# 11A-10.net
KiCad netlist of a schematic drawn in EAGLE
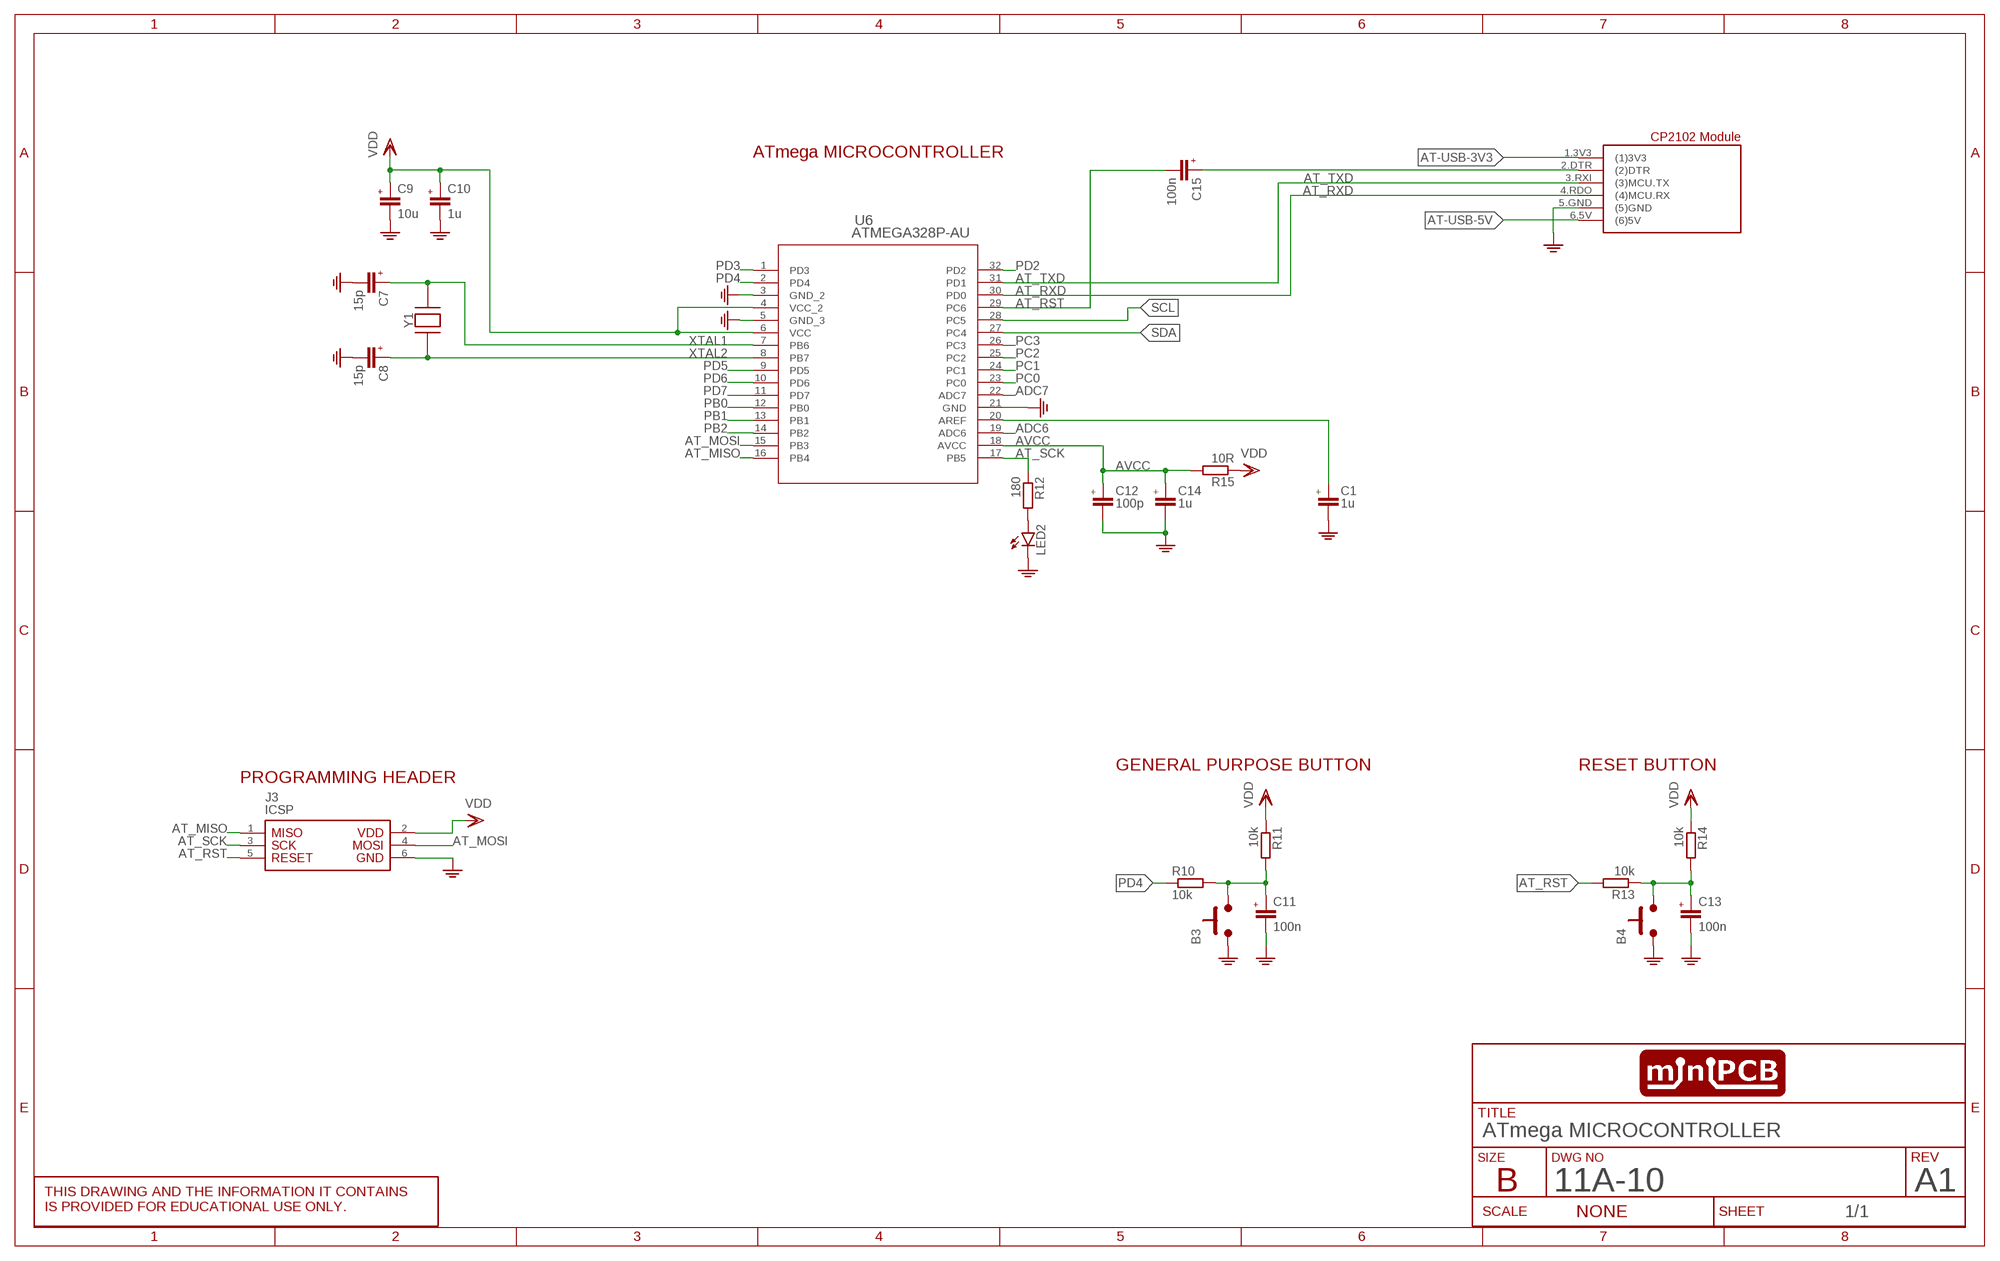
[diagram p0: schematic, sheet 1]

(export (version "E")
  (design (tool "Eeschema 10.0.6"))
  (components
    (comp (ref "B3")
      (value "PUSHBUTTON6X6MM")
      (footprint "eagle-import:6X6MM")
      (libsource (lib "eagle-import") (part "PUSHBUTTON6X6MM"))
    )
    (comp (ref "B4")
      (value "PUSHBUTTON6X6MM")
      (footprint "eagle-import:6X6MM")
      (libsource (lib "eagle-import") (part "PUSHBUTTON6X6MM"))
    )
    (comp (ref "C1")
      (value "1u")
      (footprint "eagle-import:C0805")
      (libsource (lib "eagle-import") (part "C-EU_C0805"))
    )
    (comp (ref "C7")
      (value "15p")
      (footprint "eagle-import:C0603")
      (libsource (lib "eagle-import") (part "C0603"))
    )
    (comp (ref "C8")
      (value "15p")
      (footprint "eagle-import:C0603")
      (libsource (lib "eagle-import") (part "C0603"))
    )
    (comp (ref "C9")
      (value "10u")
      (footprint "eagle-import:C0805")
      (libsource (lib "eagle-import") (part "C0805"))
    )
    (comp (ref "C10")
      (value "1u")
      (footprint "eagle-import:C0805")
      (libsource (lib "eagle-import") (part "C0805"))
    )
    (comp (ref "C11")
      (value "100n")
      (footprint "eagle-import:C0805")
      (libsource (lib "eagle-import") (part "C0805"))
    )
    (comp (ref "C12")
      (value "100p")
      (footprint "eagle-import:C0805")
      (libsource (lib "eagle-import") (part "C-EU_C0805"))
    )
    (comp (ref "C13")
      (value "100n")
      (footprint "eagle-import:C0805")
      (libsource (lib "eagle-import") (part "C0805"))
    )
    (comp (ref "C14")
      (value "1u")
      (footprint "eagle-import:C0805")
      (libsource (lib "eagle-import") (part "C-EU_C0805"))
    )
    (comp (ref "C15")
      (value "100n")
      (footprint "eagle-import:C0805")
      (libsource (lib "eagle-import") (part "C0805"))
    )
    (comp (ref "J3")
      (value "ICSP")
      (footprint "eagle-import:PINS_6-2X3_AT")
      (fields
        (field (name "P1") "P1 NAME")
        (field (name "P3") "P3 NAME")
        (field (name "P5") "P5 NAME")
        (field (name "P2") "P2 NAME")
        (field (name "P4") "P4 NAME")
        (field (name "P6") "P6 NAME")
        (field (name "P1_1") "MISO")
        (field (name "P2_1") "VDD")
        (field (name "P3_1") "SCK")
        (field (name "P4_1") "MOSI")
        (field (name "P5_1") "RESET")
        (field (name "P6_1") "GND")
      )
      (libsource (lib "eagle-import") (part "PINS_6-2X3_AT"))
    )
    (comp (ref "LED2")
      (value "LEDSML0805")
      (footprint "eagle-import:SML0805")
      (libsource (lib "eagle-import") (part "LEDSML0805"))
    )
    (comp (ref "R10")
      (value "10k")
      (footprint "eagle-import:R0805")
      (libsource (lib "eagle-import") (part "R-EU__R0805"))
    )
    (comp (ref "R11")
      (value "10k")
      (footprint "eagle-import:R0805")
      (libsource (lib "eagle-import") (part "R-EU__R0805"))
    )
    (comp (ref "R12")
      (value "180")
      (footprint "eagle-import:R0805")
      (libsource (lib "eagle-import") (part "R-EU__R0805"))
    )
    (comp (ref "R13")
      (value "10k")
      (footprint "eagle-import:R0805")
      (libsource (lib "eagle-import") (part "R-EU__R0805"))
    )
    (comp (ref "R14")
      (value "10k")
      (footprint "eagle-import:R0805")
      (libsource (lib "eagle-import") (part "R-EU__R0805"))
    )
    (comp (ref "R15")
      (value "10R")
      (footprint "eagle-import:R0805")
      (libsource (lib "eagle-import") (part "R-EU__R0805"))
    )
    (comp (ref "U6")
      (value "ATMEGA328P-AU")
      (footprint "eagle-import:32A_ATM")
      (fields
        (field (name "MANUFACTURER_PART_NUMBER") "ATMEGA328-AU")
        (field (name "COPYRIGHT") "Copyright (C) 2021 Ultra Librarian. All rights reserved.")
      )
      (libsource (lib "eagle-import") (part "ATMEGA328-AU"))
    )
    (comp (ref "U7")
      (value "VIVA_USB-TTL")
      (footprint "eagle-import:VIVA_USB_TTL_SUBTEXT")
      (libsource (lib "eagle-import") (part "VIVA_USB-TTL"))
    )
    (comp (ref "Y1")
      (value "CRYSTAL-3225_4P")
      (footprint "eagle-import:TXC7M2")
      (libsource (lib "eagle-import") (part "CRYSTAL-3225_4P"))
    )
  )
  (nets
    (net (code "1") (name "/ADC6") (class "Default")
      (node (ref "U6") (pin "19") (pinfunction "ADC6_19") (pintype "passive"))
    )
    (net (code "2") (name "/ADC7") (class "Default")
      (node (ref "U6") (pin "22") (pinfunction "ADC7_22") (pintype "passive"))
    )
    (net (code "3") (name "/AT_MISO") (class "Default")
      (node (ref "J3") (pin "1") (pinfunction "1_1") (pintype "bidirectional"))
      (node (ref "U6") (pin "16") (pinfunction "PB4_16") (pintype "bidirectional"))
    )
    (net (code "4") (name "/AT_MOSI") (class "Default")
      (node (ref "J3") (pin "4") (pinfunction "4_4") (pintype "bidirectional"))
      (node (ref "U6") (pin "15") (pinfunction "PB3_15") (pintype "bidirectional"))
    )
    (net (code "5") (name "/AT_RXD") (class "Default")
      (node (ref "U6") (pin "30") (pinfunction "PD0_30") (pintype "bidirectional"))
      (node (ref "U7") (pin "4.RDO") (pinfunction "(4)MCU.RX_4.RDO") (pintype "bidirectional"))
    )
    (net (code "6") (name "/AT_SCK") (class "Default")
      (node (ref "J3") (pin "3") (pinfunction "3_3") (pintype "bidirectional"))
      (node (ref "R12") (pin "1") (pinfunction "1_1") (pintype "passive"))
      (node (ref "U6") (pin "17") (pinfunction "PB5_17") (pintype "bidirectional"))
    )
    (net (code "7") (name "/AT_TXD") (class "Default")
      (node (ref "U6") (pin "31") (pinfunction "PD1_31") (pintype "bidirectional"))
      (node (ref "U7") (pin "3.RXI") (pinfunction "(3)MCU.TX_3.RXI") (pintype "bidirectional"))
    )
    (net (code "8") (name "/AVCC") (class "Default")
      (node (ref "C12") (pin "1") (pinfunction "1_1") (pintype "passive"))
      (node (ref "C14") (pin "1") (pinfunction "1_1") (pintype "passive"))
      (node (ref "R15") (pin "2") (pinfunction "2_2") (pintype "passive"))
      (node (ref "U6") (pin "18") (pinfunction "AVCC_18") (pintype "power_in"))
    )
    (net (code "9") (name "/PB0") (class "Default")
      (node (ref "U6") (pin "12") (pinfunction "PB0_12") (pintype "bidirectional"))
    )
    (net (code "10") (name "/PB1") (class "Default")
      (node (ref "U6") (pin "13") (pinfunction "PB1_13") (pintype "bidirectional"))
    )
    (net (code "11") (name "/PB2") (class "Default")
      (node (ref "U6") (pin "14") (pinfunction "PB2_14") (pintype "bidirectional"))
    )
    (net (code "12") (name "/PC0") (class "Default")
      (node (ref "U6") (pin "23") (pinfunction "PC0_23") (pintype "bidirectional"))
    )
    (net (code "13") (name "/PC1") (class "Default")
      (node (ref "U6") (pin "24") (pinfunction "PC1_24") (pintype "bidirectional"))
    )
    (net (code "14") (name "/PC2") (class "Default")
      (node (ref "U6") (pin "25") (pinfunction "PC2_25") (pintype "bidirectional"))
    )
    (net (code "15") (name "/PC3") (class "Default")
      (node (ref "U6") (pin "26") (pinfunction "PC3_26") (pintype "bidirectional"))
    )
    (net (code "16") (name "/PD2") (class "Default")
      (node (ref "U6") (pin "32") (pinfunction "PD2_32") (pintype "bidirectional"))
    )
    (net (code "17") (name "/PD3") (class "Default")
      (node (ref "U6") (pin "1") (pinfunction "PD3_1") (pintype "bidirectional"))
    )
    (net (code "18") (name "/PD5") (class "Default")
      (node (ref "U6") (pin "9") (pinfunction "PD5_9") (pintype "bidirectional"))
    )
    (net (code "19") (name "/PD6") (class "Default")
      (node (ref "U6") (pin "10") (pinfunction "PD6_10") (pintype "bidirectional"))
    )
    (net (code "20") (name "/PD7") (class "Default")
      (node (ref "U6") (pin "11") (pinfunction "PD7_11") (pintype "bidirectional"))
    )
    (net (code "21") (name "/XTAL1") (class "Default")
      (node (ref "C7") (pin "2") (pinfunction "+_2") (pintype "passive"))
      (node (ref "U6") (pin "7") (pinfunction "PB6_7") (pintype "bidirectional"))
      (node (ref "Y1") (pin "3") (pinfunction "2_3") (pintype "bidirectional"))
    )
    (net (code "22") (name "/XTAL2") (class "Default")
      (node (ref "C8") (pin "2") (pinfunction "+_2") (pintype "passive"))
      (node (ref "U6") (pin "8") (pinfunction "PB7_8") (pintype "bidirectional"))
      (node (ref "Y1") (pin "1") (pinfunction "1_1") (pintype "bidirectional"))
    )
    (net (code "23") (name "AT-USB-3V3") (class "Default")
      (node (ref "U7") (pin "1.3V3") (pinfunction "(1)3V3_1.3V3") (pintype "bidirectional"))
    )
    (net (code "24") (name "AT-USB-5V") (class "Default")
      (node (ref "U7") (pin "6.5V") (pinfunction "(6)5V_6.5V") (pintype "bidirectional"))
    )
    (net (code "25") (name "AT_RST") (class "Default")
      (node (ref "C15") (pin "2") (pinfunction "-_2") (pintype "passive"))
      (node (ref "J3") (pin "5") (pinfunction "5_5") (pintype "bidirectional"))
      (node (ref "R13") (pin "2") (pinfunction "2_2") (pintype "passive"))
      (node (ref "U6") (pin "29") (pinfunction "PC6_29") (pintype "bidirectional"))
    )
    (net (code "26") (name "GND") (class "Default")
      (node (ref "B3") (pin "1.A") (pinfunction "1_1.A") (pintype "bidirectional"))
      (node (ref "B3") (pin "2.A") (pinfunction "1_2.A") (pintype "bidirectional"))
      (node (ref "B4") (pin "1.A") (pinfunction "1_1.A") (pintype "bidirectional"))
      (node (ref "B4") (pin "2.A") (pinfunction "1_2.A") (pintype "bidirectional"))
      (node (ref "C1") (pin "2") (pinfunction "2_2") (pintype "passive"))
      (node (ref "C10") (pin "2") (pinfunction "-_2") (pintype "passive"))
      (node (ref "C11") (pin "2") (pinfunction "-_2") (pintype "passive"))
      (node (ref "C12") (pin "2") (pinfunction "2_2") (pintype "passive"))
      (node (ref "C13") (pin "2") (pinfunction "-_2") (pintype "passive"))
      (node (ref "C14") (pin "2") (pinfunction "2_2") (pintype "passive"))
      (node (ref "C7") (pin "1") (pinfunction "-_1") (pintype "passive"))
      (node (ref "C8") (pin "1") (pinfunction "-_1") (pintype "passive"))
      (node (ref "C9") (pin "2") (pinfunction "-_2") (pintype "passive"))
      (node (ref "J3") (pin "6") (pinfunction "6_6") (pintype "bidirectional"))
      (node (ref "LED2") (pin "C") (pinfunction "C_C") (pintype "passive"))
      (node (ref "U6") (pin "21") (pinfunction "GND_21") (pintype "power_in"))
      (node (ref "U6") (pin "3") (pinfunction "GND_2_3") (pintype "power_in"))
      (node (ref "U6") (pin "5") (pinfunction "GND_3_5") (pintype "power_in"))
      (node (ref "U7") (pin "5.GND") (pinfunction "(5)GND_5.GND") (pintype "bidirectional"))
    )
    (net (code "27") (name "Net-(C11-+)") (class "Default")
      (node (ref "B3") (pin "3.B") (pinfunction "2_3.B") (pintype "bidirectional"))
      (node (ref "B3") (pin "4.B") (pinfunction "2_4.B") (pintype "bidirectional"))
      (node (ref "C11") (pin "1") (pinfunction "+_1") (pintype "passive"))
      (node (ref "R10") (pin "2") (pinfunction "2_2") (pintype "passive"))
      (node (ref "R11") (pin "2") (pinfunction "2_2") (pintype "passive"))
    )
    (net (code "28") (name "Net-(C13-+)") (class "Default")
      (node (ref "B4") (pin "3.B") (pinfunction "2_3.B") (pintype "bidirectional"))
      (node (ref "B4") (pin "4.B") (pinfunction "2_4.B") (pintype "bidirectional"))
      (node (ref "C13") (pin "1") (pinfunction "+_1") (pintype "passive"))
      (node (ref "R13") (pin "1") (pinfunction "1_1") (pintype "passive"))
      (node (ref "R14") (pin "2") (pinfunction "2_2") (pintype "passive"))
    )
    (net (code "29") (name "Net-(C15-+)") (class "Default")
      (node (ref "C15") (pin "1") (pinfunction "+_1") (pintype "passive"))
      (node (ref "U7") (pin "2.DTR") (pinfunction "(2)DTR_2.DTR") (pintype "bidirectional"))
    )
    (net (code "30") (name "Net-(LED2-PadA)") (class "Default")
      (node (ref "LED2") (pin "A") (pinfunction "A_A") (pintype "passive"))
      (node (ref "R12") (pin "2") (pinfunction "2_2") (pintype "passive"))
    )
    (net (code "31") (name "Net-(U6-AREF)") (class "Default")
      (node (ref "C1") (pin "1") (pinfunction "1_1") (pintype "passive"))
      (node (ref "U6") (pin "20") (pinfunction "AREF_20") (pintype "passive"))
    )
    (net (code "32") (name "PD4") (class "Default")
      (node (ref "R10") (pin "1") (pinfunction "1_1") (pintype "passive"))
      (node (ref "U6") (pin "2") (pinfunction "PD4_2") (pintype "bidirectional"))
    )
    (net (code "33") (name "SCL") (class "Default")
      (node (ref "U6") (pin "28") (pinfunction "PC5_28") (pintype "bidirectional"))
    )
    (net (code "34") (name "SDA") (class "Default")
      (node (ref "U6") (pin "27") (pinfunction "PC4_27") (pintype "bidirectional"))
    )
    (net (code "35") (name "VDD") (class "Default")
      (node (ref "C10") (pin "1") (pinfunction "+_1") (pintype "passive"))
      (node (ref "C9") (pin "1") (pinfunction "+_1") (pintype "passive"))
      (node (ref "J3") (pin "2") (pinfunction "2_2") (pintype "bidirectional"))
      (node (ref "R11") (pin "1") (pinfunction "1_1") (pintype "passive"))
      (node (ref "R14") (pin "1") (pinfunction "1_1") (pintype "passive"))
      (node (ref "R15") (pin "1") (pinfunction "1_1") (pintype "passive"))
      (node (ref "U6") (pin "4") (pinfunction "VCC_2_4") (pintype "power_in"))
      (node (ref "U6") (pin "6") (pinfunction "VCC_6") (pintype "power_in"))
    )
  )
)
